# Push_Pull_Drivers.net
KiCad netlist of a schematic drawn in Altium Designer
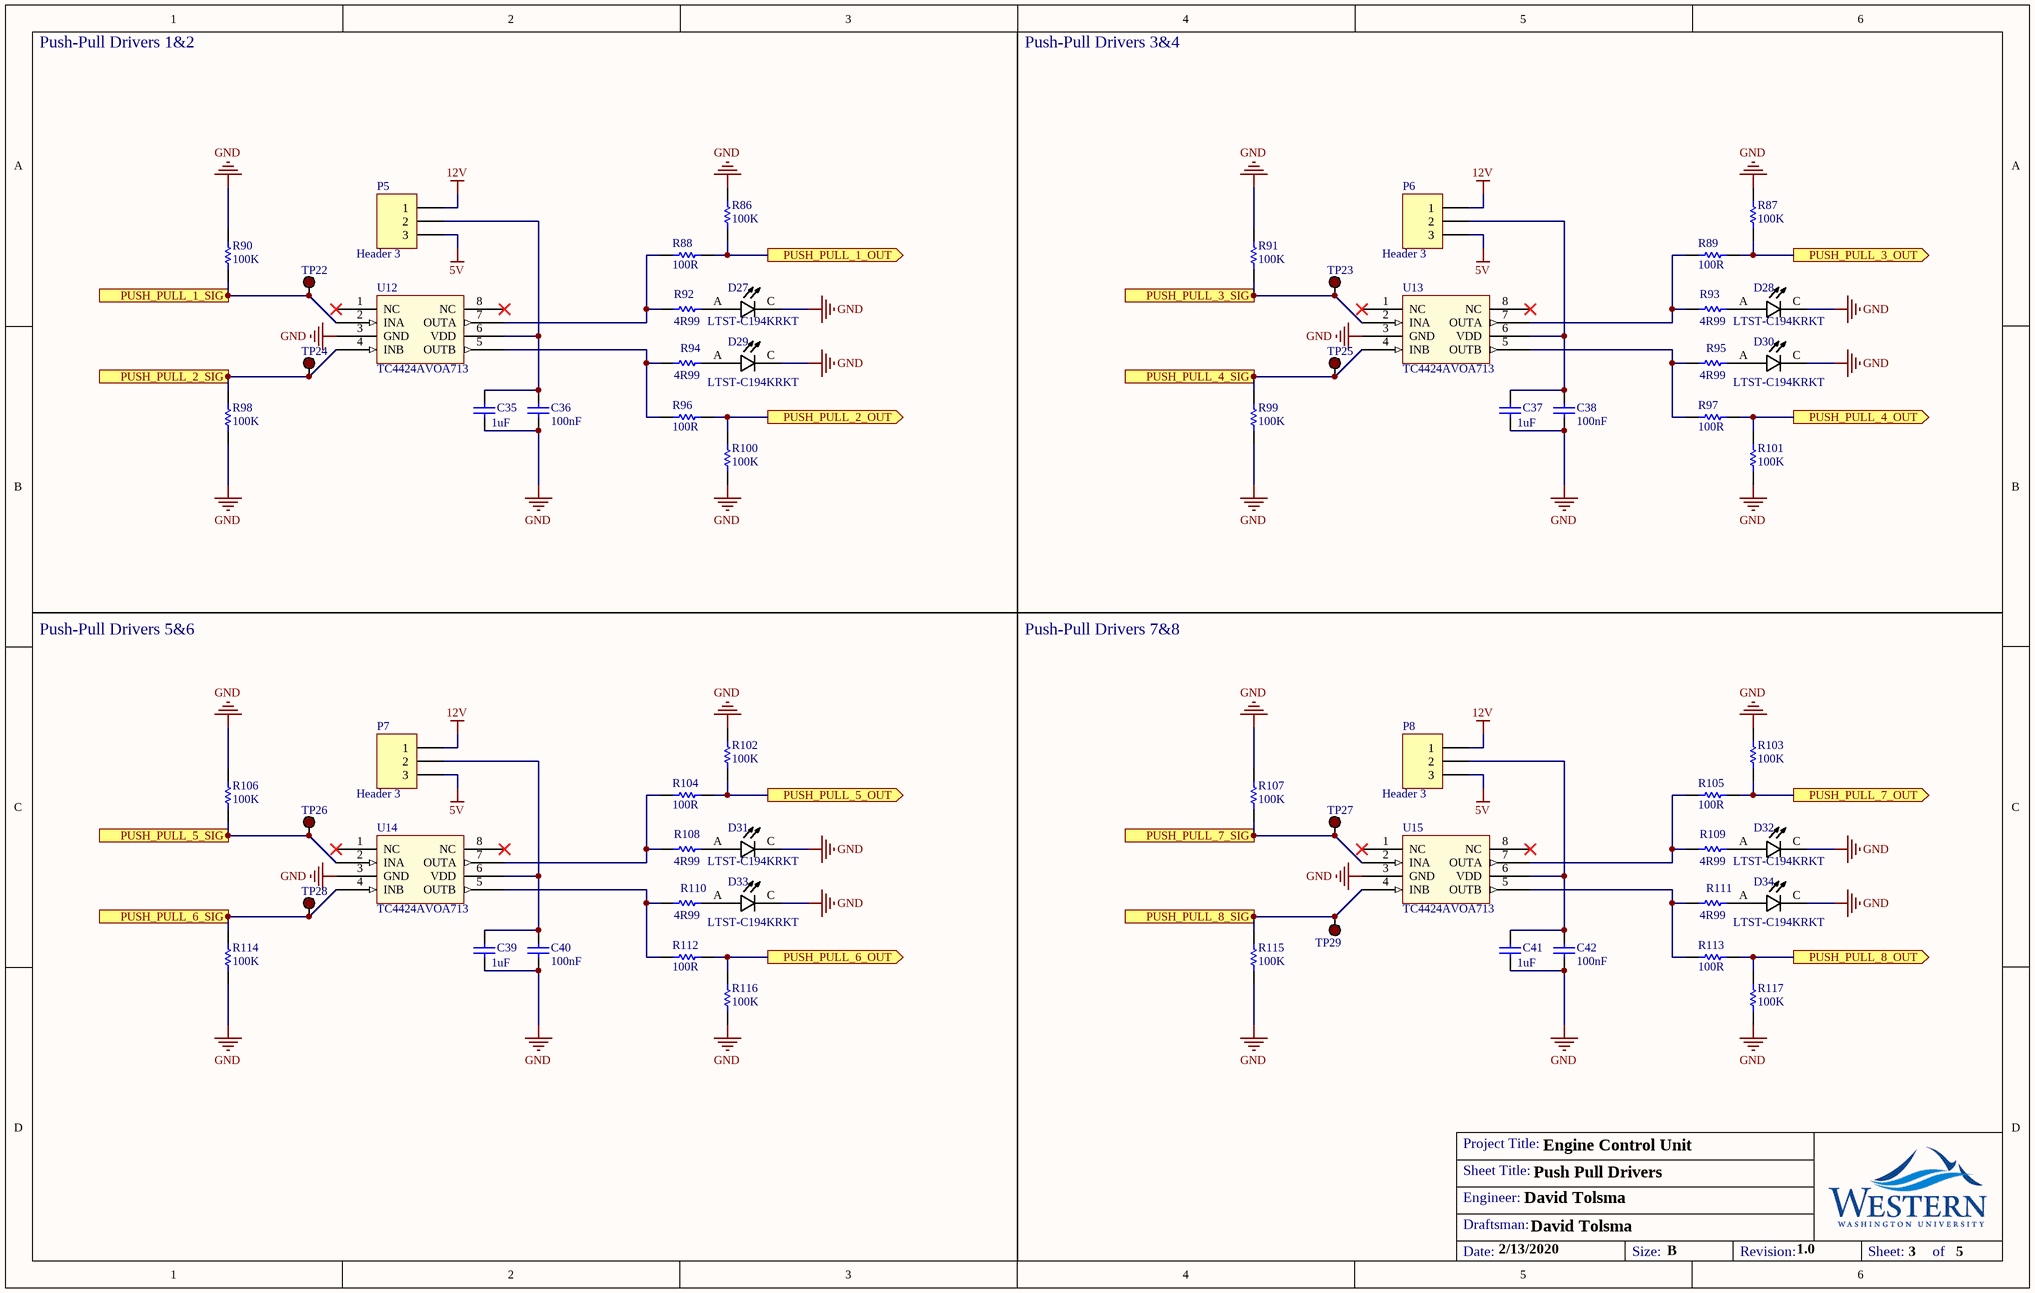
[diagram p0: Push_Pull_Drivers.SchDoc]

(export (version "E")
  (design (tool "Eeschema 10.0.6"))
  (components
    (comp (ref "C35")
      (value "1uF")
      (footprint "CAPC0603(1608)100_M")
      (description "CAP 1uF 50V ±10% 0603 (1608 Metric) Thickness 1mm SMD")
      (fields (field (name "TOLERANCE") "Â±10%"))
      (libsource (lib "Altium Content Vault") (part "CAP"))
    )
    (comp (ref "C36")
      (value "100nF")
      (footprint "CAPC0603(1608)100_M")
      (description "CAP 100nF 50V ±10% 0603 (1608 Metric) Thickness 1mm SMD")
      (fields (field (name "TOLERANCE") "Â±10%"))
      (libsource (lib "Altium Content Vault") (part "CAP"))
    )
    (comp (ref "C37")
      (value "1uF")
      (footprint "CAPC0603(1608)100_M")
      (description "CAP 1uF 50V ±10% 0603 (1608 Metric) Thickness 1mm SMD")
      (fields (field (name "TOLERANCE") "Â±10%"))
      (libsource (lib "Altium Content Vault") (part "CAP"))
    )
    (comp (ref "C38")
      (value "100nF")
      (footprint "CAPC0603(1608)100_M")
      (description "CAP 100nF 50V ±10% 0603 (1608 Metric) Thickness 1mm SMD")
      (fields (field (name "TOLERANCE") "Â±10%"))
      (libsource (lib "Altium Content Vault") (part "CAP"))
    )
    (comp (ref "C39")
      (value "1uF")
      (footprint "CAPC0603(1608)100_M")
      (description "CAP 1uF 50V ±10% 0603 (1608 Metric) Thickness 1mm SMD")
      (fields (field (name "TOLERANCE") "Â±10%"))
      (libsource (lib "Altium Content Vault") (part "CAP"))
    )
    (comp (ref "C40")
      (value "100nF")
      (footprint "CAPC0603(1608)100_M")
      (description "CAP 100nF 50V ±10% 0603 (1608 Metric) Thickness 1mm SMD")
      (fields (field (name "TOLERANCE") "Â±10%"))
      (libsource (lib "Altium Content Vault") (part "CAP"))
    )
    (comp (ref "C41")
      (value "1uF")
      (footprint "CAPC0603(1608)100_M")
      (description "CAP 1uF 50V ±10% 0603 (1608 Metric) Thickness 1mm SMD")
      (fields (field (name "TOLERANCE") "Â±10%"))
      (libsource (lib "Altium Content Vault") (part "CAP"))
    )
    (comp (ref "C42")
      (value "100nF")
      (footprint "CAPC0603(1608)100_M")
      (description "CAP 100nF 50V ±10% 0603 (1608 Metric) Thickness 1mm SMD")
      (fields (field (name "TOLERANCE") "Â±10%"))
      (libsource (lib "Altium Content Vault") (part "CAP"))
    )
    (comp (ref "D27")
      (value "LTST-C194KRKT")
      (footprint "LEDC1608X35N_LTST-C194KRKT")
      (description "Red 631nm LED Indication - Discrete 2V 0603 _1608 Metric_")
      (fields (field (name "MF") "Lite-On Inc.") (field (name "DIGI-KEY_PART_NUMBER") "160-1835-1-ND"))
      (libsource (lib "ECU") (part "LTST-C194KRKT"))
    )
    (comp (ref "D28")
      (value "LTST-C194KRKT")
      (footprint "LEDC1608X35N_LTST-C194KRKT")
      (description "Red 631nm LED Indication - Discrete 2V 0603 _1608 Metric_")
      (fields (field (name "MF") "Lite-On Inc.") (field (name "DIGI-KEY_PART_NUMBER") "160-1835-1-ND"))
      (libsource (lib "ECU") (part "LTST-C194KRKT"))
    )
    (comp (ref "D29")
      (value "LTST-C194KRKT")
      (footprint "LEDC1608X35N_LTST-C194KRKT")
      (description "Red 631nm LED Indication - Discrete 2V 0603 _1608 Metric_")
      (fields (field (name "MF") "Lite-On Inc.") (field (name "DIGI-KEY_PART_NUMBER") "160-1835-1-ND"))
      (libsource (lib "ECU") (part "LTST-C194KRKT"))
    )
    (comp (ref "D30")
      (value "LTST-C194KRKT")
      (footprint "LEDC1608X35N_LTST-C194KRKT")
      (description "Red 631nm LED Indication - Discrete 2V 0603 _1608 Metric_")
      (fields (field (name "MF") "Lite-On Inc.") (field (name "DIGI-KEY_PART_NUMBER") "160-1835-1-ND"))
      (libsource (lib "ECU") (part "LTST-C194KRKT"))
    )
    (comp (ref "D31")
      (value "LTST-C194KRKT")
      (footprint "LEDC1608X35N_LTST-C194KRKT")
      (description "Red 631nm LED Indication - Discrete 2V 0603 _1608 Metric_")
      (fields (field (name "MF") "Lite-On Inc.") (field (name "DIGI-KEY_PART_NUMBER") "160-1835-1-ND"))
      (libsource (lib "ECU") (part "LTST-C194KRKT"))
    )
    (comp (ref "D32")
      (value "LTST-C194KRKT")
      (footprint "LEDC1608X35N_LTST-C194KRKT")
      (description "Red 631nm LED Indication - Discrete 2V 0603 _1608 Metric_")
      (fields (field (name "MF") "Lite-On Inc.") (field (name "DIGI-KEY_PART_NUMBER") "160-1835-1-ND"))
      (libsource (lib "ECU") (part "LTST-C194KRKT"))
    )
    (comp (ref "D33")
      (value "LTST-C194KRKT")
      (footprint "LEDC1608X35N_LTST-C194KRKT")
      (description "Red 631nm LED Indication - Discrete 2V 0603 _1608 Metric_")
      (fields (field (name "MF") "Lite-On Inc.") (field (name "DIGI-KEY_PART_NUMBER") "160-1835-1-ND"))
      (libsource (lib "ECU") (part "LTST-C194KRKT"))
    )
    (comp (ref "D34")
      (value "LTST-C194KRKT")
      (footprint "LEDC1608X35N_LTST-C194KRKT")
      (description "Red 631nm LED Indication - Discrete 2V 0603 _1608 Metric_")
      (fields (field (name "MF") "Lite-On Inc.") (field (name "DIGI-KEY_PART_NUMBER") "160-1835-1-ND"))
      (libsource (lib "ECU") (part "LTST-C194KRKT"))
    )
    (comp (ref "P5")
      (value "Header 3")
      (footprint "HDR1X3")
      (description "Header, 3-Pin")
      (fields (field (name "PUBLISHER") "Altium Limited"))
      (libsource (lib "Miscellaneous Connectors") (part "Header 3"))
    )
    (comp (ref "P6")
      (value "Header 3")
      (footprint "HDR1X3")
      (description "Header, 3-Pin")
      (fields (field (name "PUBLISHER") "Altium Limited"))
      (libsource (lib "Miscellaneous Connectors") (part "Header 3"))
    )
    (comp (ref "P7")
      (value "Header 3")
      (footprint "HDR1X3")
      (description "Header, 3-Pin")
      (fields (field (name "PUBLISHER") "Altium Limited"))
      (libsource (lib "Miscellaneous Connectors") (part "Header 3"))
    )
    (comp (ref "P8")
      (value "Header 3")
      (footprint "HDR1X3")
      (description "Header, 3-Pin")
      (fields (field (name "PUBLISHER") "Altium Limited"))
      (libsource (lib "Miscellaneous Connectors") (part "Header 3"))
    )
    (comp (ref "R86")
      (value "100K")
      (footprint "RESC0603(1608)_M")
      (description "100K 0.1W 1% 0603 (1608 Metric)  SMD")
      (fields (field (name "POWER") "0.1 W") (field (name "TOLERANCE") "1 %"))
      (libsource (lib "Altium Content Vault") (part "RES"))
    )
    (comp (ref "R87")
      (value "100K")
      (footprint "RESC0603(1608)_M")
      (description "100K 0.1W 1% 0603 (1608 Metric)  SMD")
      (fields (field (name "POWER") "0.1 W") (field (name "TOLERANCE") "1 %"))
      (libsource (lib "Altium Content Vault") (part "RES"))
    )
    (comp (ref "R88")
      (value "100R")
      (footprint "RESC1206(3216)_L")
      (description "100R 0.25W 1% 1206 (3216 Metric)  SMD")
      (fields (field (name "TOLERANCE") "1 %") (field (name "POWER") "0.25 W"))
      (libsource (lib "Altium Content Vault") (part "RES"))
    )
    (comp (ref "R89")
      (value "100R")
      (footprint "RESC1206(3216)_L")
      (description "100R 0.25W 1% 1206 (3216 Metric)  SMD")
      (fields (field (name "TOLERANCE") "1 %") (field (name "POWER") "0.25 W"))
      (libsource (lib "Altium Content Vault") (part "RES"))
    )
    (comp (ref "R90")
      (value "100K")
      (footprint "RESC0603(1608)_M")
      (description "100K 0.1W 1% 0603 (1608 Metric)  SMD")
      (fields (field (name "POWER") "0.1 W") (field (name "TOLERANCE") "1 %"))
      (libsource (lib "Altium Content Vault") (part "RES"))
    )
    (comp (ref "R91")
      (value "100K")
      (footprint "RESC0603(1608)_M")
      (description "100K 0.1W 1% 0603 (1608 Metric)  SMD")
      (fields (field (name "POWER") "0.1 W") (field (name "TOLERANCE") "1 %"))
      (libsource (lib "Altium Content Vault") (part "RES"))
    )
    (comp (ref "R92")
      (value "4R99")
      (footprint "RESC0603(1608)_M")
      (description "4R99 0.1W 1% 0603 (1608 Metric)  SMD")
      (fields (field (name "TOLERANCE") "1 %") (field (name "POWER") "0.1 W"))
      (libsource (lib "Altium Content Vault") (part "RES"))
    )
    (comp (ref "R93")
      (value "4R99")
      (footprint "RESC0603(1608)_M")
      (description "4R99 0.1W 1% 0603 (1608 Metric)  SMD")
      (fields (field (name "TOLERANCE") "1 %") (field (name "POWER") "0.1 W"))
      (libsource (lib "Altium Content Vault") (part "RES"))
    )
    (comp (ref "R94")
      (value "4R99")
      (footprint "RESC0603(1608)_M")
      (description "4R99 0.1W 1% 0603 (1608 Metric)  SMD")
      (fields (field (name "TOLERANCE") "1 %") (field (name "POWER") "0.1 W"))
      (libsource (lib "Altium Content Vault") (part "RES"))
    )
    (comp (ref "R95")
      (value "4R99")
      (footprint "RESC0603(1608)_M")
      (description "4R99 0.1W 1% 0603 (1608 Metric)  SMD")
      (fields (field (name "TOLERANCE") "1 %") (field (name "POWER") "0.1 W"))
      (libsource (lib "Altium Content Vault") (part "RES"))
    )
    (comp (ref "R96")
      (value "100R")
      (footprint "RESC1206(3216)_L")
      (description "100R 0.25W 1% 1206 (3216 Metric)  SMD")
      (fields (field (name "TOLERANCE") "1 %") (field (name "POWER") "0.25 W"))
      (libsource (lib "Altium Content Vault") (part "RES"))
    )
    (comp (ref "R97")
      (value "100R")
      (footprint "RESC1206(3216)_L")
      (description "100R 0.25W 1% 1206 (3216 Metric)  SMD")
      (fields (field (name "TOLERANCE") "1 %") (field (name "POWER") "0.25 W"))
      (libsource (lib "Altium Content Vault") (part "RES"))
    )
    (comp (ref "R98")
      (value "100K")
      (footprint "RESC0603(1608)_M")
      (description "100K 0.1W 1% 0603 (1608 Metric)  SMD")
      (fields (field (name "POWER") "0.1 W") (field (name "TOLERANCE") "1 %"))
      (libsource (lib "Altium Content Vault") (part "RES"))
    )
    (comp (ref "R99")
      (value "100K")
      (footprint "RESC0603(1608)_M")
      (description "100K 0.1W 1% 0603 (1608 Metric)  SMD")
      (fields (field (name "POWER") "0.1 W") (field (name "TOLERANCE") "1 %"))
      (libsource (lib "Altium Content Vault") (part "RES"))
    )
    (comp (ref "R100")
      (value "100K")
      (footprint "RESC0603(1608)_M")
      (description "100K 0.1W 1% 0603 (1608 Metric)  SMD")
      (fields (field (name "POWER") "0.1 W") (field (name "TOLERANCE") "1 %"))
      (libsource (lib "Altium Content Vault") (part "RES"))
    )
    (comp (ref "R101")
      (value "100K")
      (footprint "RESC0603(1608)_M")
      (description "100K 0.1W 1% 0603 (1608 Metric)  SMD")
      (fields (field (name "POWER") "0.1 W") (field (name "TOLERANCE") "1 %"))
      (libsource (lib "Altium Content Vault") (part "RES"))
    )
    (comp (ref "R102")
      (value "100K")
      (footprint "RESC0603(1608)_M")
      (description "100K 0.1W 1% 0603 (1608 Metric)  SMD")
      (fields (field (name "POWER") "0.1 W") (field (name "TOLERANCE") "1 %"))
      (libsource (lib "Altium Content Vault") (part "RES"))
    )
    (comp (ref "R103")
      (value "100K")
      (footprint "RESC0603(1608)_M")
      (description "100K 0.1W 1% 0603 (1608 Metric)  SMD")
      (fields (field (name "POWER") "0.1 W") (field (name "TOLERANCE") "1 %"))
      (libsource (lib "Altium Content Vault") (part "RES"))
    )
    (comp (ref "R104")
      (value "100R")
      (footprint "RESC1206(3216)_L")
      (description "100R 0.25W 1% 1206 (3216 Metric)  SMD")
      (fields (field (name "TOLERANCE") "1 %") (field (name "POWER") "0.25 W"))
      (libsource (lib "Altium Content Vault") (part "RES"))
    )
    (comp (ref "R105")
      (value "100R")
      (footprint "RESC1206(3216)_L")
      (description "100R 0.25W 1% 1206 (3216 Metric)  SMD")
      (fields (field (name "TOLERANCE") "1 %") (field (name "POWER") "0.25 W"))
      (libsource (lib "Altium Content Vault") (part "RES"))
    )
    (comp (ref "R106")
      (value "100K")
      (footprint "RESC0603(1608)_M")
      (description "100K 0.1W 1% 0603 (1608 Metric)  SMD")
      (fields (field (name "POWER") "0.1 W") (field (name "TOLERANCE") "1 %"))
      (libsource (lib "Altium Content Vault") (part "RES"))
    )
    (comp (ref "R107")
      (value "100K")
      (footprint "RESC0603(1608)_M")
      (description "100K 0.1W 1% 0603 (1608 Metric)  SMD")
      (fields (field (name "POWER") "0.1 W") (field (name "TOLERANCE") "1 %"))
      (libsource (lib "Altium Content Vault") (part "RES"))
    )
    (comp (ref "R108")
      (value "4R99")
      (footprint "RESC0603(1608)_M")
      (description "4R99 0.1W 1% 0603 (1608 Metric)  SMD")
      (fields (field (name "TOLERANCE") "1 %") (field (name "POWER") "0.1 W"))
      (libsource (lib "Altium Content Vault") (part "RES"))
    )
    (comp (ref "R109")
      (value "4R99")
      (footprint "RESC0603(1608)_M")
      (description "4R99 0.1W 1% 0603 (1608 Metric)  SMD")
      (fields (field (name "TOLERANCE") "1 %") (field (name "POWER") "0.1 W"))
      (libsource (lib "Altium Content Vault") (part "RES"))
    )
    (comp (ref "R110")
      (value "4R99")
      (footprint "RESC0603(1608)_M")
      (description "4R99 0.1W 1% 0603 (1608 Metric)  SMD")
      (fields (field (name "TOLERANCE") "1 %") (field (name "POWER") "0.1 W"))
      (libsource (lib "Altium Content Vault") (part "RES"))
    )
    (comp (ref "R111")
      (value "4R99")
      (footprint "RESC0603(1608)_M")
      (description "4R99 0.1W 1% 0603 (1608 Metric)  SMD")
      (fields (field (name "TOLERANCE") "1 %") (field (name "POWER") "0.1 W"))
      (libsource (lib "Altium Content Vault") (part "RES"))
    )
    (comp (ref "R112")
      (value "100R")
      (footprint "RESC1206(3216)_L")
      (description "100R 0.25W 1% 1206 (3216 Metric)  SMD")
      (fields (field (name "TOLERANCE") "1 %") (field (name "POWER") "0.25 W"))
      (libsource (lib "Altium Content Vault") (part "RES"))
    )
    (comp (ref "R113")
      (value "100R")
      (footprint "RESC1206(3216)_L")
      (description "100R 0.25W 1% 1206 (3216 Metric)  SMD")
      (fields (field (name "TOLERANCE") "1 %") (field (name "POWER") "0.25 W"))
      (libsource (lib "Altium Content Vault") (part "RES"))
    )
    (comp (ref "R114")
      (value "100K")
      (footprint "RESC0603(1608)_M")
      (description "100K 0.1W 1% 0603 (1608 Metric)  SMD")
      (fields (field (name "POWER") "0.1 W") (field (name "TOLERANCE") "1 %"))
      (libsource (lib "Altium Content Vault") (part "RES"))
    )
    (comp (ref "R115")
      (value "100K")
      (footprint "RESC0603(1608)_M")
      (description "100K 0.1W 1% 0603 (1608 Metric)  SMD")
      (fields (field (name "POWER") "0.1 W") (field (name "TOLERANCE") "1 %"))
      (libsource (lib "Altium Content Vault") (part "RES"))
    )
    (comp (ref "R116")
      (value "100K")
      (footprint "RESC0603(1608)_M")
      (description "100K 0.1W 1% 0603 (1608 Metric)  SMD")
      (fields (field (name "POWER") "0.1 W") (field (name "TOLERANCE") "1 %"))
      (libsource (lib "Altium Content Vault") (part "RES"))
    )
    (comp (ref "R117")
      (value "100K")
      (footprint "RESC0603(1608)_M")
      (description "100K 0.1W 1% 0603 (1608 Metric)  SMD")
      (fields (field (name "POWER") "0.1 W") (field (name "TOLERANCE") "1 %"))
      (libsource (lib "Altium Content Vault") (part "RES"))
    )
    (comp (ref "TP22")
      (value "5001")
      (footprint "Keystone_5001")
      (description "TEST POINT PC MINI .040\"D BLACK")
      (fields (field (name "MANUFACTURER") "Keystone Electronics"))
      (libsource (lib "WWUEE_SchematicLibrary") (part "TEST POINT"))
    )
    (comp (ref "TP23")
      (value "5001")
      (footprint "Keystone_5001")
      (description "TEST POINT PC MINI .040\"D BLACK")
      (fields (field (name "MANUFACTURER") "Keystone Electronics"))
      (libsource (lib "WWUEE_SchematicLibrary") (part "TEST POINT"))
    )
    (comp (ref "TP24")
      (value "5001")
      (footprint "Keystone_5001")
      (description "TEST POINT PC MINI .040\"D BLACK")
      (fields (field (name "MANUFACTURER") "Keystone Electronics"))
      (libsource (lib "WWUEE_SchematicLibrary") (part "TEST POINT"))
    )
    (comp (ref "TP25")
      (value "5001")
      (footprint "Keystone_5001")
      (description "TEST POINT PC MINI .040\"D BLACK")
      (fields (field (name "MANUFACTURER") "Keystone Electronics"))
      (libsource (lib "WWUEE_SchematicLibrary") (part "TEST POINT"))
    )
    (comp (ref "TP26")
      (value "5001")
      (footprint "Keystone_5001")
      (description "TEST POINT PC MINI .040\"D BLACK")
      (fields (field (name "MANUFACTURER") "Keystone Electronics"))
      (libsource (lib "WWUEE_SchematicLibrary") (part "TEST POINT"))
    )
    (comp (ref "TP27")
      (value "5001")
      (footprint "Keystone_5001")
      (description "TEST POINT PC MINI .040\"D BLACK")
      (fields (field (name "MANUFACTURER") "Keystone Electronics"))
      (libsource (lib "WWUEE_SchematicLibrary") (part "TEST POINT"))
    )
    (comp (ref "TP28")
      (value "5001")
      (footprint "Keystone_5001")
      (description "TEST POINT PC MINI .040\"D BLACK")
      (fields (field (name "MANUFACTURER") "Keystone Electronics"))
      (libsource (lib "WWUEE_SchematicLibrary") (part "TEST POINT"))
    )
    (comp (ref "TP29")
      (value "5001")
      (footprint "Keystone_5001")
      (description "TEST POINT PC MINI .040\"D BLACK")
      (fields (field (name "MANUFACTURER") "Keystone Electronics"))
      (libsource (lib "WWUEE_SchematicLibrary") (part "TEST POINT"))
    )
    (comp (ref "U12")
      (value "TC4424AVOA713")
      (footprint "TC4424AVOA713")
      (libsource (lib "ECU") (part "TC4424AVOA713"))
    )
    (comp (ref "U13")
      (value "TC4424AVOA713")
      (footprint "TC4424AVOA713")
      (libsource (lib "ECU") (part "TC4424AVOA713"))
    )
    (comp (ref "U14")
      (value "TC4424AVOA713")
      (footprint "TC4424AVOA713")
      (libsource (lib "ECU") (part "TC4424AVOA713"))
    )
    (comp (ref "U15")
      (value "TC4424AVOA713")
      (footprint "TC4424AVOA713")
      (libsource (lib "ECU") (part "TC4424AVOA713"))
    )
  )
  (nets
    (net (code "1") (name "/PUSH_PULL_1_OUT") (class "Default")
      (node (ref "R86") (pin "1") (pinfunction "1_1") (pintype "passive"))
      (node (ref "R88") (pin "2") (pinfunction "2_2") (pintype "passive"))
    )
    (net (code "2") (name "/PUSH_PULL_1_SIG") (class "Default")
      (node (ref "R90") (pin "2") (pinfunction "2_2") (pintype "passive"))
      (node (ref "TP22") (pin "1") (pinfunction "TP_1") (pintype "passive"))
      (node (ref "U12") (pin "2") (pinfunction "INA_2") (pintype "input"))
    )
    (net (code "3") (name "/PUSH_PULL_2_OUT") (class "Default")
      (node (ref "R100") (pin "2") (pinfunction "2_2") (pintype "passive"))
      (node (ref "R96") (pin "2") (pinfunction "2_2") (pintype "passive"))
    )
    (net (code "4") (name "/PUSH_PULL_2_SIG") (class "Default")
      (node (ref "R98") (pin "2") (pinfunction "2_2") (pintype "passive"))
      (node (ref "TP24") (pin "1") (pinfunction "TP_1") (pintype "passive"))
      (node (ref "U12") (pin "4") (pinfunction "INB_4") (pintype "input"))
    )
    (net (code "5") (name "/PUSH_PULL_3_OUT") (class "Default")
      (node (ref "R87") (pin "1") (pinfunction "1_1") (pintype "passive"))
      (node (ref "R89") (pin "2") (pinfunction "2_2") (pintype "passive"))
    )
    (net (code "6") (name "/PUSH_PULL_3_SIG") (class "Default")
      (node (ref "R91") (pin "2") (pinfunction "2_2") (pintype "passive"))
      (node (ref "TP23") (pin "1") (pinfunction "TP_1") (pintype "passive"))
      (node (ref "U13") (pin "2") (pinfunction "INA_2") (pintype "input"))
    )
    (net (code "7") (name "/PUSH_PULL_4_OUT") (class "Default")
      (node (ref "R101") (pin "2") (pinfunction "2_2") (pintype "passive"))
      (node (ref "R97") (pin "2") (pinfunction "2_2") (pintype "passive"))
    )
    (net (code "8") (name "/PUSH_PULL_4_SIG") (class "Default")
      (node (ref "R99") (pin "2") (pinfunction "2_2") (pintype "passive"))
      (node (ref "TP25") (pin "1") (pinfunction "TP_1") (pintype "passive"))
      (node (ref "U13") (pin "4") (pinfunction "INB_4") (pintype "input"))
    )
    (net (code "9") (name "/PUSH_PULL_5_OUT") (class "Default")
      (node (ref "R102") (pin "1") (pinfunction "1_1") (pintype "passive"))
      (node (ref "R104") (pin "2") (pinfunction "2_2") (pintype "passive"))
    )
    (net (code "10") (name "/PUSH_PULL_5_SIG") (class "Default")
      (node (ref "R106") (pin "2") (pinfunction "2_2") (pintype "passive"))
      (node (ref "TP26") (pin "1") (pinfunction "TP_1") (pintype "passive"))
      (node (ref "U14") (pin "2") (pinfunction "INA_2") (pintype "input"))
    )
    (net (code "11") (name "/PUSH_PULL_6_OUT") (class "Default")
      (node (ref "R112") (pin "2") (pinfunction "2_2") (pintype "passive"))
      (node (ref "R116") (pin "2") (pinfunction "2_2") (pintype "passive"))
    )
    (net (code "12") (name "/PUSH_PULL_6_SIG") (class "Default")
      (node (ref "R114") (pin "2") (pinfunction "2_2") (pintype "passive"))
      (node (ref "TP28") (pin "1") (pinfunction "TP_1") (pintype "passive"))
      (node (ref "U14") (pin "4") (pinfunction "INB_4") (pintype "input"))
    )
    (net (code "13") (name "/PUSH_PULL_7_OUT") (class "Default")
      (node (ref "R103") (pin "1") (pinfunction "1_1") (pintype "passive"))
      (node (ref "R105") (pin "2") (pinfunction "2_2") (pintype "passive"))
    )
    (net (code "14") (name "/PUSH_PULL_7_SIG") (class "Default")
      (node (ref "R107") (pin "2") (pinfunction "2_2") (pintype "passive"))
      (node (ref "TP27") (pin "1") (pinfunction "TP_1") (pintype "passive"))
      (node (ref "U15") (pin "2") (pinfunction "INA_2") (pintype "input"))
    )
    (net (code "15") (name "/PUSH_PULL_8_OUT") (class "Default")
      (node (ref "R113") (pin "2") (pinfunction "2_2") (pintype "passive"))
      (node (ref "R117") (pin "2") (pinfunction "2_2") (pintype "passive"))
    )
    (net (code "16") (name "/PUSH_PULL_8_SIG") (class "Default")
      (node (ref "R115") (pin "2") (pinfunction "2_2") (pintype "passive"))
      (node (ref "TP29") (pin "1") (pinfunction "TP_1") (pintype "passive"))
      (node (ref "U15") (pin "4") (pinfunction "INB_4") (pintype "input"))
    )
    (net (code "17") (name "5V") (class "Default")
      (node (ref "P5") (pin "3") (pinfunction "3_3") (pintype "passive"))
      (node (ref "P6") (pin "3") (pinfunction "3_3") (pintype "passive"))
      (node (ref "P7") (pin "3") (pinfunction "3_3") (pintype "passive"))
      (node (ref "P8") (pin "3") (pinfunction "3_3") (pintype "passive"))
    )
    (net (code "18") (name "12V") (class "Default")
      (node (ref "P5") (pin "1") (pinfunction "1_1") (pintype "passive"))
      (node (ref "P6") (pin "1") (pinfunction "1_1") (pintype "passive"))
      (node (ref "P7") (pin "1") (pinfunction "1_1") (pintype "passive"))
      (node (ref "P8") (pin "1") (pinfunction "1_1") (pintype "passive"))
    )
    (net (code "19") (name "GND") (class "Default")
      (node (ref "C35") (pin "1") (pinfunction "1_1") (pintype "passive"))
      (node (ref "C36") (pin "1") (pinfunction "1_1") (pintype "passive"))
      (node (ref "C37") (pin "1") (pinfunction "1_1") (pintype "passive"))
      (node (ref "C38") (pin "1") (pinfunction "1_1") (pintype "passive"))
      (node (ref "C39") (pin "1") (pinfunction "1_1") (pintype "passive"))
      (node (ref "C40") (pin "1") (pinfunction "1_1") (pintype "passive"))
      (node (ref "C41") (pin "1") (pinfunction "1_1") (pintype "passive"))
      (node (ref "C42") (pin "1") (pinfunction "1_1") (pintype "passive"))
      (node (ref "D27") (pin "C") (pinfunction "C_C") (pintype "passive"))
      (node (ref "D28") (pin "C") (pinfunction "C_C") (pintype "passive"))
      (node (ref "D29") (pin "C") (pinfunction "C_C") (pintype "passive"))
      (node (ref "D30") (pin "C") (pinfunction "C_C") (pintype "passive"))
      (node (ref "D31") (pin "C") (pinfunction "C_C") (pintype "passive"))
      (node (ref "D32") (pin "C") (pinfunction "C_C") (pintype "passive"))
      (node (ref "D33") (pin "C") (pinfunction "C_C") (pintype "passive"))
      (node (ref "D34") (pin "C") (pinfunction "C_C") (pintype "passive"))
      (node (ref "R100") (pin "1") (pinfunction "1_1") (pintype "passive"))
      (node (ref "R101") (pin "1") (pinfunction "1_1") (pintype "passive"))
      (node (ref "R102") (pin "2") (pinfunction "2_2") (pintype "passive"))
      (node (ref "R103") (pin "2") (pinfunction "2_2") (pintype "passive"))
      (node (ref "R106") (pin "1") (pinfunction "1_1") (pintype "passive"))
      (node (ref "R107") (pin "1") (pinfunction "1_1") (pintype "passive"))
      (node (ref "R114") (pin "1") (pinfunction "1_1") (pintype "passive"))
      (node (ref "R115") (pin "1") (pinfunction "1_1") (pintype "passive"))
      (node (ref "R116") (pin "1") (pinfunction "1_1") (pintype "passive"))
      (node (ref "R117") (pin "1") (pinfunction "1_1") (pintype "passive"))
      (node (ref "R86") (pin "2") (pinfunction "2_2") (pintype "passive"))
      (node (ref "R87") (pin "2") (pinfunction "2_2") (pintype "passive"))
      (node (ref "R90") (pin "1") (pinfunction "1_1") (pintype "passive"))
      (node (ref "R91") (pin "1") (pinfunction "1_1") (pintype "passive"))
      (node (ref "R98") (pin "1") (pinfunction "1_1") (pintype "passive"))
      (node (ref "R99") (pin "1") (pinfunction "1_1") (pintype "passive"))
      (node (ref "U12") (pin "3") (pinfunction "GND_3") (pintype "power_in"))
      (node (ref "U13") (pin "3") (pinfunction "GND_3") (pintype "power_in"))
      (node (ref "U14") (pin "3") (pinfunction "GND_3") (pintype "power_in"))
      (node (ref "U15") (pin "3") (pinfunction "GND_3") (pintype "power_in"))
    )
    (net (code "20") (name "Net-(D27-PadA)") (class "Default")
      (node (ref "D27") (pin "A") (pinfunction "A_A") (pintype "passive"))
      (node (ref "R92") (pin "2") (pinfunction "2_2") (pintype "passive"))
    )
    (net (code "21") (name "Net-(D28-PadA)") (class "Default")
      (node (ref "D28") (pin "A") (pinfunction "A_A") (pintype "passive"))
      (node (ref "R93") (pin "2") (pinfunction "2_2") (pintype "passive"))
    )
    (net (code "22") (name "Net-(D29-PadA)") (class "Default")
      (node (ref "D29") (pin "A") (pinfunction "A_A") (pintype "passive"))
      (node (ref "R94") (pin "2") (pinfunction "2_2") (pintype "passive"))
    )
    (net (code "23") (name "Net-(D30-PadA)") (class "Default")
      (node (ref "D30") (pin "A") (pinfunction "A_A") (pintype "passive"))
      (node (ref "R95") (pin "2") (pinfunction "2_2") (pintype "passive"))
    )
    (net (code "24") (name "Net-(D31-PadA)") (class "Default")
      (node (ref "D31") (pin "A") (pinfunction "A_A") (pintype "passive"))
      (node (ref "R108") (pin "2") (pinfunction "2_2") (pintype "passive"))
    )
    (net (code "25") (name "Net-(D32-PadA)") (class "Default")
      (node (ref "D32") (pin "A") (pinfunction "A_A") (pintype "passive"))
      (node (ref "R109") (pin "2") (pinfunction "2_2") (pintype "passive"))
    )
    (net (code "26") (name "Net-(D33-PadA)") (class "Default")
      (node (ref "D33") (pin "A") (pinfunction "A_A") (pintype "passive"))
      (node (ref "R110") (pin "2") (pinfunction "2_2") (pintype "passive"))
    )
    (net (code "27") (name "Net-(D34-PadA)") (class "Default")
      (node (ref "D34") (pin "A") (pinfunction "A_A") (pintype "passive"))
      (node (ref "R111") (pin "2") (pinfunction "2_2") (pintype "passive"))
    )
    (net (code "28") (name "Net-(U12-OUTA)") (class "Default")
      (node (ref "R88") (pin "1") (pinfunction "1_1") (pintype "passive"))
      (node (ref "R92") (pin "1") (pinfunction "1_1") (pintype "passive"))
      (node (ref "U12") (pin "7") (pinfunction "OUTA_7") (pintype "output"))
    )
    (net (code "29") (name "Net-(U12-OUTB)") (class "Default")
      (node (ref "R94") (pin "1") (pinfunction "1_1") (pintype "passive"))
      (node (ref "R96") (pin "1") (pinfunction "1_1") (pintype "passive"))
      (node (ref "U12") (pin "5") (pinfunction "OUTB_5") (pintype "output"))
    )
    (net (code "30") (name "Net-(U12-VDD)") (class "Default")
      (node (ref "C35") (pin "2") (pinfunction "2_2") (pintype "passive"))
      (node (ref "C36") (pin "2") (pinfunction "2_2") (pintype "passive"))
      (node (ref "P5") (pin "2") (pinfunction "2_2") (pintype "passive"))
      (node (ref "U12") (pin "6") (pinfunction "VDD_6") (pintype "power_in"))
    )
    (net (code "31") (name "Net-(U13-OUTA)") (class "Default")
      (node (ref "R89") (pin "1") (pinfunction "1_1") (pintype "passive"))
      (node (ref "R93") (pin "1") (pinfunction "1_1") (pintype "passive"))
      (node (ref "U13") (pin "7") (pinfunction "OUTA_7") (pintype "output"))
    )
    (net (code "32") (name "Net-(U13-OUTB)") (class "Default")
      (node (ref "R95") (pin "1") (pinfunction "1_1") (pintype "passive"))
      (node (ref "R97") (pin "1") (pinfunction "1_1") (pintype "passive"))
      (node (ref "U13") (pin "5") (pinfunction "OUTB_5") (pintype "output"))
    )
    (net (code "33") (name "Net-(U13-VDD)") (class "Default")
      (node (ref "C37") (pin "2") (pinfunction "2_2") (pintype "passive"))
      (node (ref "C38") (pin "2") (pinfunction "2_2") (pintype "passive"))
      (node (ref "P6") (pin "2") (pinfunction "2_2") (pintype "passive"))
      (node (ref "U13") (pin "6") (pinfunction "VDD_6") (pintype "power_in"))
    )
    (net (code "34") (name "Net-(U14-OUTA)") (class "Default")
      (node (ref "R104") (pin "1") (pinfunction "1_1") (pintype "passive"))
      (node (ref "R108") (pin "1") (pinfunction "1_1") (pintype "passive"))
      (node (ref "U14") (pin "7") (pinfunction "OUTA_7") (pintype "output"))
    )
    (net (code "35") (name "Net-(U14-OUTB)") (class "Default")
      (node (ref "R110") (pin "1") (pinfunction "1_1") (pintype "passive"))
      (node (ref "R112") (pin "1") (pinfunction "1_1") (pintype "passive"))
      (node (ref "U14") (pin "5") (pinfunction "OUTB_5") (pintype "output"))
    )
    (net (code "36") (name "Net-(U14-VDD)") (class "Default")
      (node (ref "C39") (pin "2") (pinfunction "2_2") (pintype "passive"))
      (node (ref "C40") (pin "2") (pinfunction "2_2") (pintype "passive"))
      (node (ref "P7") (pin "2") (pinfunction "2_2") (pintype "passive"))
      (node (ref "U14") (pin "6") (pinfunction "VDD_6") (pintype "power_in"))
    )
    (net (code "37") (name "Net-(U15-OUTA)") (class "Default")
      (node (ref "R105") (pin "1") (pinfunction "1_1") (pintype "passive"))
      (node (ref "R109") (pin "1") (pinfunction "1_1") (pintype "passive"))
      (node (ref "U15") (pin "7") (pinfunction "OUTA_7") (pintype "output"))
    )
    (net (code "38") (name "Net-(U15-OUTB)") (class "Default")
      (node (ref "R111") (pin "1") (pinfunction "1_1") (pintype "passive"))
      (node (ref "R113") (pin "1") (pinfunction "1_1") (pintype "passive"))
      (node (ref "U15") (pin "5") (pinfunction "OUTB_5") (pintype "output"))
    )
    (net (code "39") (name "Net-(U15-VDD)") (class "Default")
      (node (ref "C41") (pin "2") (pinfunction "2_2") (pintype "passive"))
      (node (ref "C42") (pin "2") (pinfunction "2_2") (pintype "passive"))
      (node (ref "P8") (pin "2") (pinfunction "2_2") (pintype "passive"))
      (node (ref "U15") (pin "6") (pinfunction "VDD_6") (pintype "power_in"))
    )
    (net (code "40") (name "unconnected-(U12-NC-Pad1)") (class "Default")
      (node (ref "U12") (pin "1") (pinfunction "NC_1") (pintype "tri_state+no_connect"))
    )
    (net (code "41") (name "unconnected-(U12-NC-Pad8)") (class "Default")
      (node (ref "U12") (pin "8") (pinfunction "NC_8") (pintype "tri_state+no_connect"))
    )
    (net (code "42") (name "unconnected-(U13-NC-Pad1)") (class "Default")
      (node (ref "U13") (pin "1") (pinfunction "NC_1") (pintype "tri_state+no_connect"))
    )
    (net (code "43") (name "unconnected-(U13-NC-Pad8)") (class "Default")
      (node (ref "U13") (pin "8") (pinfunction "NC_8") (pintype "tri_state+no_connect"))
    )
    (net (code "44") (name "unconnected-(U14-NC-Pad1)") (class "Default")
      (node (ref "U14") (pin "1") (pinfunction "NC_1") (pintype "tri_state+no_connect"))
    )
    (net (code "45") (name "unconnected-(U14-NC-Pad8)") (class "Default")
      (node (ref "U14") (pin "8") (pinfunction "NC_8") (pintype "tri_state+no_connect"))
    )
    (net (code "46") (name "unconnected-(U15-NC-Pad1)") (class "Default")
      (node (ref "U15") (pin "1") (pinfunction "NC_1") (pintype "tri_state+no_connect"))
    )
    (net (code "47") (name "unconnected-(U15-NC-Pad8)") (class "Default")
      (node (ref "U15") (pin "8") (pinfunction "NC_8") (pintype "tri_state+no_connect"))
    )
  )
)
